# zdroj_schema_1.net
KiCad netlist of a schematic drawn in EAGLE
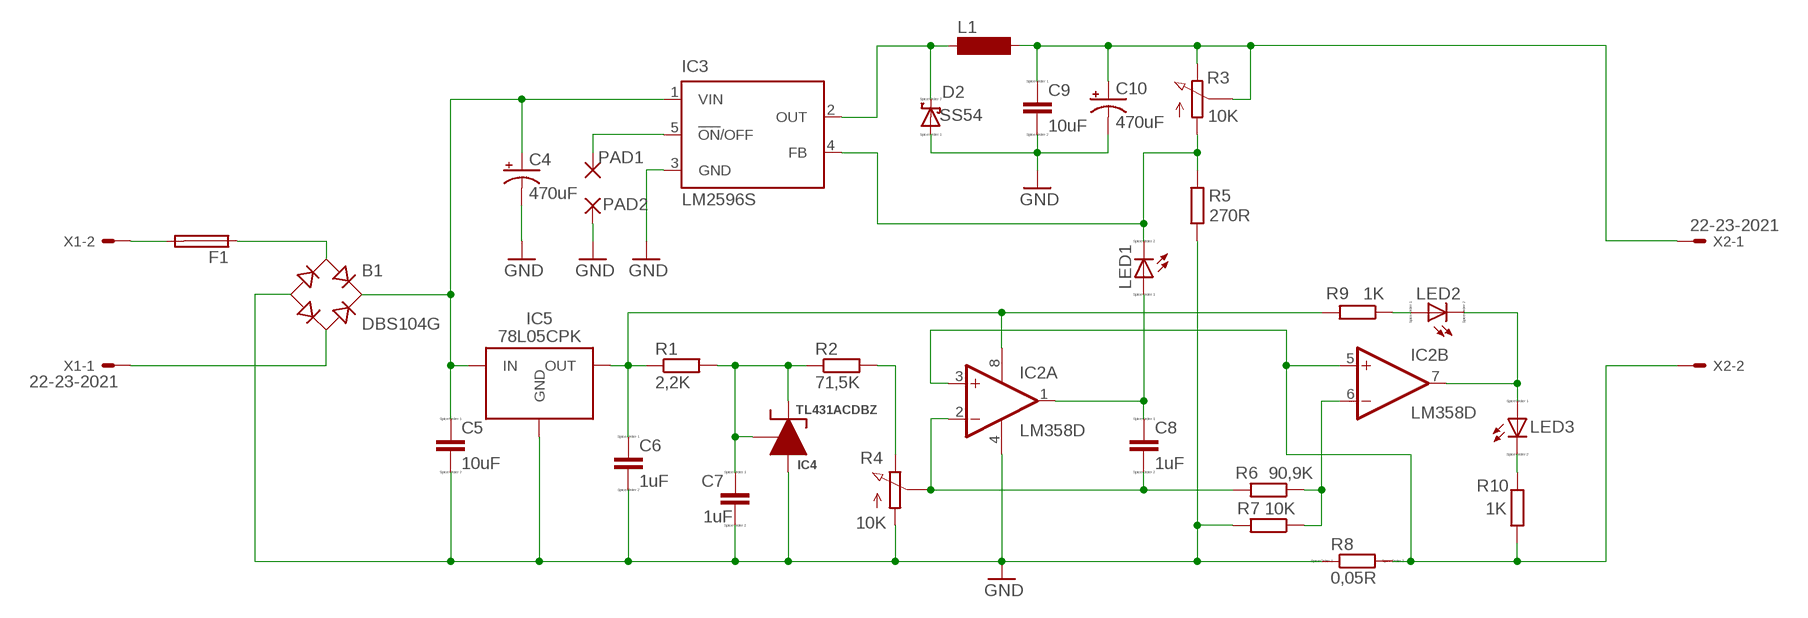
[diagram p0: schematic, sheet 1]

(export (version "E")
  (design (tool "Eeschema 10.0.6"))
  (components
    (comp (ref "B1")
      (value "DBS104G")
      (footprint "eagle-import:DBS")
      (libsource (lib "eagle-import") (part "DB?GS104"))
    )
    (comp (ref "C4")
      (value "470uF")
      (footprint "eagle-import:153CLV-0605")
      (libsource (lib "eagle-import") (part "CPOL-US153CLV-0605"))
    )
    (comp (ref "C5")
      (value "10uF")
      (footprint "eagle-import:C0805")
      (libsource (lib "eagle-import") (part "C"))
    )
    (comp (ref "C6")
      (value "1uF")
      (footprint "eagle-import:C0805")
      (libsource (lib "eagle-import") (part "C"))
    )
    (comp (ref "C7")
      (value "1uF")
      (footprint "eagle-import:C0805")
      (libsource (lib "eagle-import") (part "C"))
    )
    (comp (ref "C8")
      (value "1uF")
      (footprint "eagle-import:C0805")
      (libsource (lib "eagle-import") (part "C"))
    )
    (comp (ref "C9")
      (value "10uF")
      (footprint "eagle-import:C0805")
      (libsource (lib "eagle-import") (part "C"))
    )
    (comp (ref "C10")
      (value "470uF")
      (footprint "eagle-import:153CLV-0605")
      (libsource (lib "eagle-import") (part "CPOL-US153CLV-0605"))
    )
    (comp (ref "D2")
      (value "SS54")
      (footprint "eagle-import:DIODE_SMB")
      (libsource (lib "eagle-import") (part "SCHOTTKY-DIODE"))
    )
    (comp (ref "F1")
      (value "TE5")
      (footprint "eagle-import:TE5")
      (libsource (lib "eagle-import") (part "TE5"))
    )
    (comp (ref "IC2")
      (value "LM358D")
      (footprint "eagle-import:SO08")
      (libsource (lib "eagle-import") (part "LM358D"))
    )
    (comp (ref "IC3")
      (value "LM2596S")
      (footprint "eagle-import:TO263-5")
      (fields (field (name "MF") "NATIONAL SEMICONDUCTOR") (field (name "MPN") "LM2596S-ADJ/NOPB"))
      (libsource (lib "eagle-import") (part "LM2596S"))
    )
    (comp (ref "IC4")
      (value "TL431ACDBZ")
      (footprint "eagle-import:SOT-23")
      (fields (field (name "MF") "Texas Instruments"))
      (libsource (lib "eagle-import") (part "TL431DBZAC"))
    )
    (comp (ref "IC5")
      (value "78L05CPK")
      (footprint "eagle-import:SOT89")
      (fields (field (name "MF") "Texas Instruments") (field (name "MPN") "UA78L05CPK"))
      (libsource (lib "eagle-import") (part "78L05?PKC"))
    )
    (comp (ref "L1")
      (value "SM-L15B")
      (footprint "eagle-import:SM-L15B")
      (libsource (lib "eagle-import") (part "SM-L15B"))
    )
    (comp (ref "LED1")
      (value "LED_E")
      (footprint "eagle-import:LED_1206")
      (libsource (lib "eagle-import") (part "LED_E"))
    )
    (comp (ref "LED2")
      (value "LED_E")
      (footprint "eagle-import:LED_1206")
      (libsource (lib "eagle-import") (part "LED_E"))
    )
    (comp (ref "LED3")
      (value "LED_E")
      (footprint "eagle-import:LED_1206")
      (libsource (lib "eagle-import") (part "LED_E"))
    )
    (comp (ref "PAD1")
      (value "2,54/1,0")
      (footprint "eagle-import:2,54_1,0")
      (libsource (lib "eagle-import") (part "2,54/1,0"))
    )
    (comp (ref "PAD2")
      (value "2,54/1,0")
      (footprint "eagle-import:2,54_1,0")
      (libsource (lib "eagle-import") (part "2,54/1,0"))
    )
    (comp (ref "R1")
      (value "2,2K")
      (footprint "eagle-import:M0805")
      (libsource (lib "eagle-import") (part "R-EU_M0805"))
    )
    (comp (ref "R2")
      (value "71,5K")
      (footprint "eagle-import:M0805")
      (libsource (lib "eagle-import") (part "R-EU_M0805"))
    )
    (comp (ref "R3")
      (value "10K")
      (footprint "eagle-import:PC25")
      (fields (field (name "MF") "CLAROSTAT") (field (name "MPN") "308NPC25KS"))
      (libsource (lib "eagle-import") (part "PC25"))
    )
    (comp (ref "R4")
      (value "10K")
      (footprint "eagle-import:PC25")
      (fields (field (name "MF") "CLAROSTAT") (field (name "MPN") "308NPC25KS"))
      (libsource (lib "eagle-import") (part "PC25"))
    )
    (comp (ref "R5")
      (value "270R")
      (footprint "eagle-import:M0805")
      (libsource (lib "eagle-import") (part "R-EU_M0805"))
    )
    (comp (ref "R6")
      (value "90,9K")
      (footprint "eagle-import:M0805")
      (libsource (lib "eagle-import") (part "R-EU_M0805"))
    )
    (comp (ref "R7")
      (value "10K")
      (footprint "eagle-import:M0805")
      (libsource (lib "eagle-import") (part "R-EU_M0805"))
    )
    (comp (ref "R8")
      (value "0,05R")
      (footprint "eagle-import:R2512")
      (libsource (lib "eagle-import") (part "RR2512"))
    )
    (comp (ref "R9")
      (value "1K")
      (footprint "eagle-import:M0805")
      (libsource (lib "eagle-import") (part "R-EU_M0805"))
    )
    (comp (ref "R10")
      (value "1K")
      (footprint "eagle-import:M0805")
      (libsource (lib "eagle-import") (part "R-EU_M0805"))
    )
    (comp (ref "X1")
      (value "22-23-2021")
      (footprint "eagle-import:22-23-2021")
      (fields (field (name "MF") "MOLEX"))
      (libsource (lib "eagle-import") (part "22-23-2021"))
    )
    (comp (ref "X2")
      (value "22-23-2021")
      (footprint "eagle-import:22-23-2021")
      (fields (field (name "MF") "MOLEX"))
      (libsource (lib "eagle-import") (part "22-23-2021"))
    )
  )
  (nets
    (net (code "1") (name "GND") (class "Default")
      (node (ref "B1") (pin "-") (pinfunction "-_-") (pintype "passive"))
      (node (ref "C10") (pin "-") (pinfunction "-_-") (pintype "passive"))
      (node (ref "C4") (pin "-") (pinfunction "-_-") (pintype "passive"))
      (node (ref "C5") (pin "2") (pinfunction "2_2") (pintype "passive"))
      (node (ref "C6") (pin "2") (pinfunction "2_2") (pintype "passive"))
      (node (ref "C7") (pin "2") (pinfunction "2_2") (pintype "passive"))
      (node (ref "C9") (pin "2") (pinfunction "2_2") (pintype "passive"))
      (node (ref "D2") (pin "A") (pinfunction "C_A") (pintype "passive"))
      (node (ref "IC2") (pin "4") (pinfunction "V-_4") (pintype "power_in"))
      (node (ref "IC3") (pin "3") (pinfunction "GND_3") (pintype "power_in"))
      (node (ref "IC4") (pin "3") (pinfunction "ANODE_3") (pintype "power_in"))
      (node (ref "IC5") (pin "2") (pinfunction "GND_2") (pintype "power_in"))
      (node (ref "IC5") (pin "2@1") (pinfunction "GND_2@1") (pintype "power_in"))
      (node (ref "PAD2") (pin "1") (pinfunction "P_1") (pintype "passive"))
      (node (ref "R4") (pin "A") (pinfunction "A_A") (pintype "passive"))
      (node (ref "R5") (pin "1") (pinfunction "1_1") (pintype "passive"))
      (node (ref "R7") (pin "2") (pinfunction "2_2") (pintype "passive"))
      (node (ref "R8") (pin "1") (pinfunction "1_1") (pintype "passive"))
    )
    (net (code "2") (name "Net-(B1-PadAC1)") (class "Default")
      (node (ref "B1") (pin "AC1") (pinfunction "AC1_AC1") (pintype "passive"))
      (node (ref "F1") (pin "1") (pinfunction "1_1") (pintype "passive"))
    )
    (net (code "3") (name "Net-(D2-A)") (class "Default")
      (node (ref "D2") (pin "C") (pinfunction "A_C") (pintype "passive"))
      (node (ref "IC3") (pin "2") (pinfunction "OUT_2") (pintype "output"))
      (node (ref "L1") (pin "1") (pinfunction "1_1") (pintype "passive"))
    )
    (net (code "4") (name "Net-(IC2A-+IN)") (class "Default")
      (node (ref "IC2") (pin "3") (pinfunction "+IN_3") (pintype "input"))
      (node (ref "IC2") (pin "5") (pinfunction "+IN_5") (pintype "input"))
      (node (ref "R10") (pin "2") (pinfunction "2_2") (pintype "passive"))
      (node (ref "R8") (pin "2") (pinfunction "2_2") (pintype "passive"))
      (node (ref "X2") (pin "2") (pinfunction "S_2") (pintype "passive"))
    )
    (net (code "5") (name "Net-(IC2A--IN)") (class "Default")
      (node (ref "C8") (pin "2") (pinfunction "2_2") (pintype "passive"))
      (node (ref "IC2") (pin "2") (pinfunction "-IN_2") (pintype "input"))
      (node (ref "R4") (pin "S") (pinfunction "S_S") (pintype "passive"))
      (node (ref "R6") (pin "2") (pinfunction "2_2") (pintype "passive"))
    )
    (net (code "6") (name "Net-(IC2A-OUT)") (class "Default")
      (node (ref "C8") (pin "1") (pinfunction "1_1") (pintype "passive"))
      (node (ref "IC2") (pin "1") (pinfunction "OUT_1") (pintype "output"))
      (node (ref "LED1") (pin "A") (pinfunction "A_A") (pintype "passive"))
    )
    (net (code "7") (name "Net-(IC2B--IN)") (class "Default")
      (node (ref "IC2") (pin "6") (pinfunction "-IN_6") (pintype "input"))
      (node (ref "R6") (pin "1") (pinfunction "1_1") (pintype "passive"))
      (node (ref "R7") (pin "1") (pinfunction "1_1") (pintype "passive"))
    )
    (net (code "8") (name "Net-(IC2B-OUT)") (class "Default")
      (node (ref "IC2") (pin "7") (pinfunction "OUT_7") (pintype "output"))
      (node (ref "LED2") (pin "C") (pinfunction "C_C") (pintype "passive"))
      (node (ref "LED3") (pin "A") (pinfunction "A_A") (pintype "passive"))
    )
    (net (code "9") (name "Net-(IC2C-V+)") (class "Default")
      (node (ref "C6") (pin "1") (pinfunction "1_1") (pintype "passive"))
      (node (ref "IC2") (pin "8") (pinfunction "V+_8") (pintype "power_in"))
      (node (ref "IC5") (pin "1") (pinfunction "OUT_1") (pintype "output"))
      (node (ref "R1") (pin "1") (pinfunction "1_1") (pintype "passive"))
      (node (ref "R9") (pin "2") (pinfunction "2_2") (pintype "passive"))
    )
    (net (code "10") (name "Net-(IC3-FB)") (class "Default")
      (node (ref "IC3") (pin "4") (pinfunction "FB_4") (pintype "input"))
      (node (ref "LED1") (pin "C") (pinfunction "C_C") (pintype "passive"))
      (node (ref "R3") (pin "A") (pinfunction "A_A") (pintype "passive"))
      (node (ref "R5") (pin "2") (pinfunction "2_2") (pintype "passive"))
    )
    (net (code "11") (name "Net-(IC3-VIN)") (class "Default")
      (node (ref "B1") (pin "+") (pinfunction "+_+") (pintype "passive"))
      (node (ref "C4") (pin "+") (pinfunction "+_+") (pintype "passive"))
      (node (ref "C5") (pin "1") (pinfunction "1_1") (pintype "passive"))
      (node (ref "IC3") (pin "1") (pinfunction "VIN_1") (pintype "input"))
      (node (ref "IC5") (pin "3") (pinfunction "IN_3") (pintype "input"))
    )
    (net (code "12") (name "Net-(IC3-~{ON}{slash}OFF)") (class "Default")
      (node (ref "IC3") (pin "5") (pinfunction "~{ON}/OFF_5") (pintype "input"))
      (node (ref "PAD1") (pin "1") (pinfunction "P_1") (pintype "passive"))
    )
    (net (code "13") (name "Net-(IC4-CATHODE)") (class "Default")
      (node (ref "C7") (pin "1") (pinfunction "1_1") (pintype "passive"))
      (node (ref "IC4") (pin "1") (pinfunction "CATHODE_1") (pintype "bidirectional"))
      (node (ref "IC4") (pin "2") (pinfunction "REF_2") (pintype "input"))
      (node (ref "R1") (pin "2") (pinfunction "2_2") (pintype "passive"))
      (node (ref "R2") (pin "1") (pinfunction "1_1") (pintype "passive"))
    )
    (net (code "14") (name "Net-(LED2-PadA)") (class "Default")
      (node (ref "LED2") (pin "A") (pinfunction "A_A") (pintype "passive"))
      (node (ref "R9") (pin "1") (pinfunction "1_1") (pintype "passive"))
    )
    (net (code "15") (name "Net-(LED3-PadC)") (class "Default")
      (node (ref "LED3") (pin "C") (pinfunction "C_C") (pintype "passive"))
      (node (ref "R10") (pin "1") (pinfunction "1_1") (pintype "passive"))
    )
    (net (code "16") (name "Net-(R2-Pad2)") (class "Default")
      (node (ref "R2") (pin "2") (pinfunction "2_2") (pintype "passive"))
      (node (ref "R4") (pin "E") (pinfunction "E_E") (pintype "passive"))
    )
    (net (code "17") (name "Net-(X1A-S)") (class "Default")
      (node (ref "B1") (pin "AC2") (pinfunction "AC2_AC2") (pintype "passive"))
      (node (ref "X1") (pin "1") (pinfunction "S_1") (pintype "passive"))
    )
    (net (code "18") (name "Net-(X1B-S)") (class "Default")
      (node (ref "F1") (pin "2") (pinfunction "2_2") (pintype "passive"))
      (node (ref "X1") (pin "2") (pinfunction "S_2") (pintype "passive"))
    )
    (net (code "19") (name "Net-(X2A-S)") (class "Default")
      (node (ref "C10") (pin "+") (pinfunction "+_+") (pintype "passive"))
      (node (ref "C9") (pin "1") (pinfunction "1_1") (pintype "passive"))
      (node (ref "L1") (pin "2") (pinfunction "2_2") (pintype "passive"))
      (node (ref "R3") (pin "E") (pinfunction "E_E") (pintype "passive"))
      (node (ref "R3") (pin "S") (pinfunction "S_S") (pintype "passive"))
      (node (ref "X2") (pin "1") (pinfunction "S_1") (pintype "passive"))
    )
  )
)
